# Schematic_Smart_watch_system.net
KiCad netlist of a schematic drawn in EasyEDA
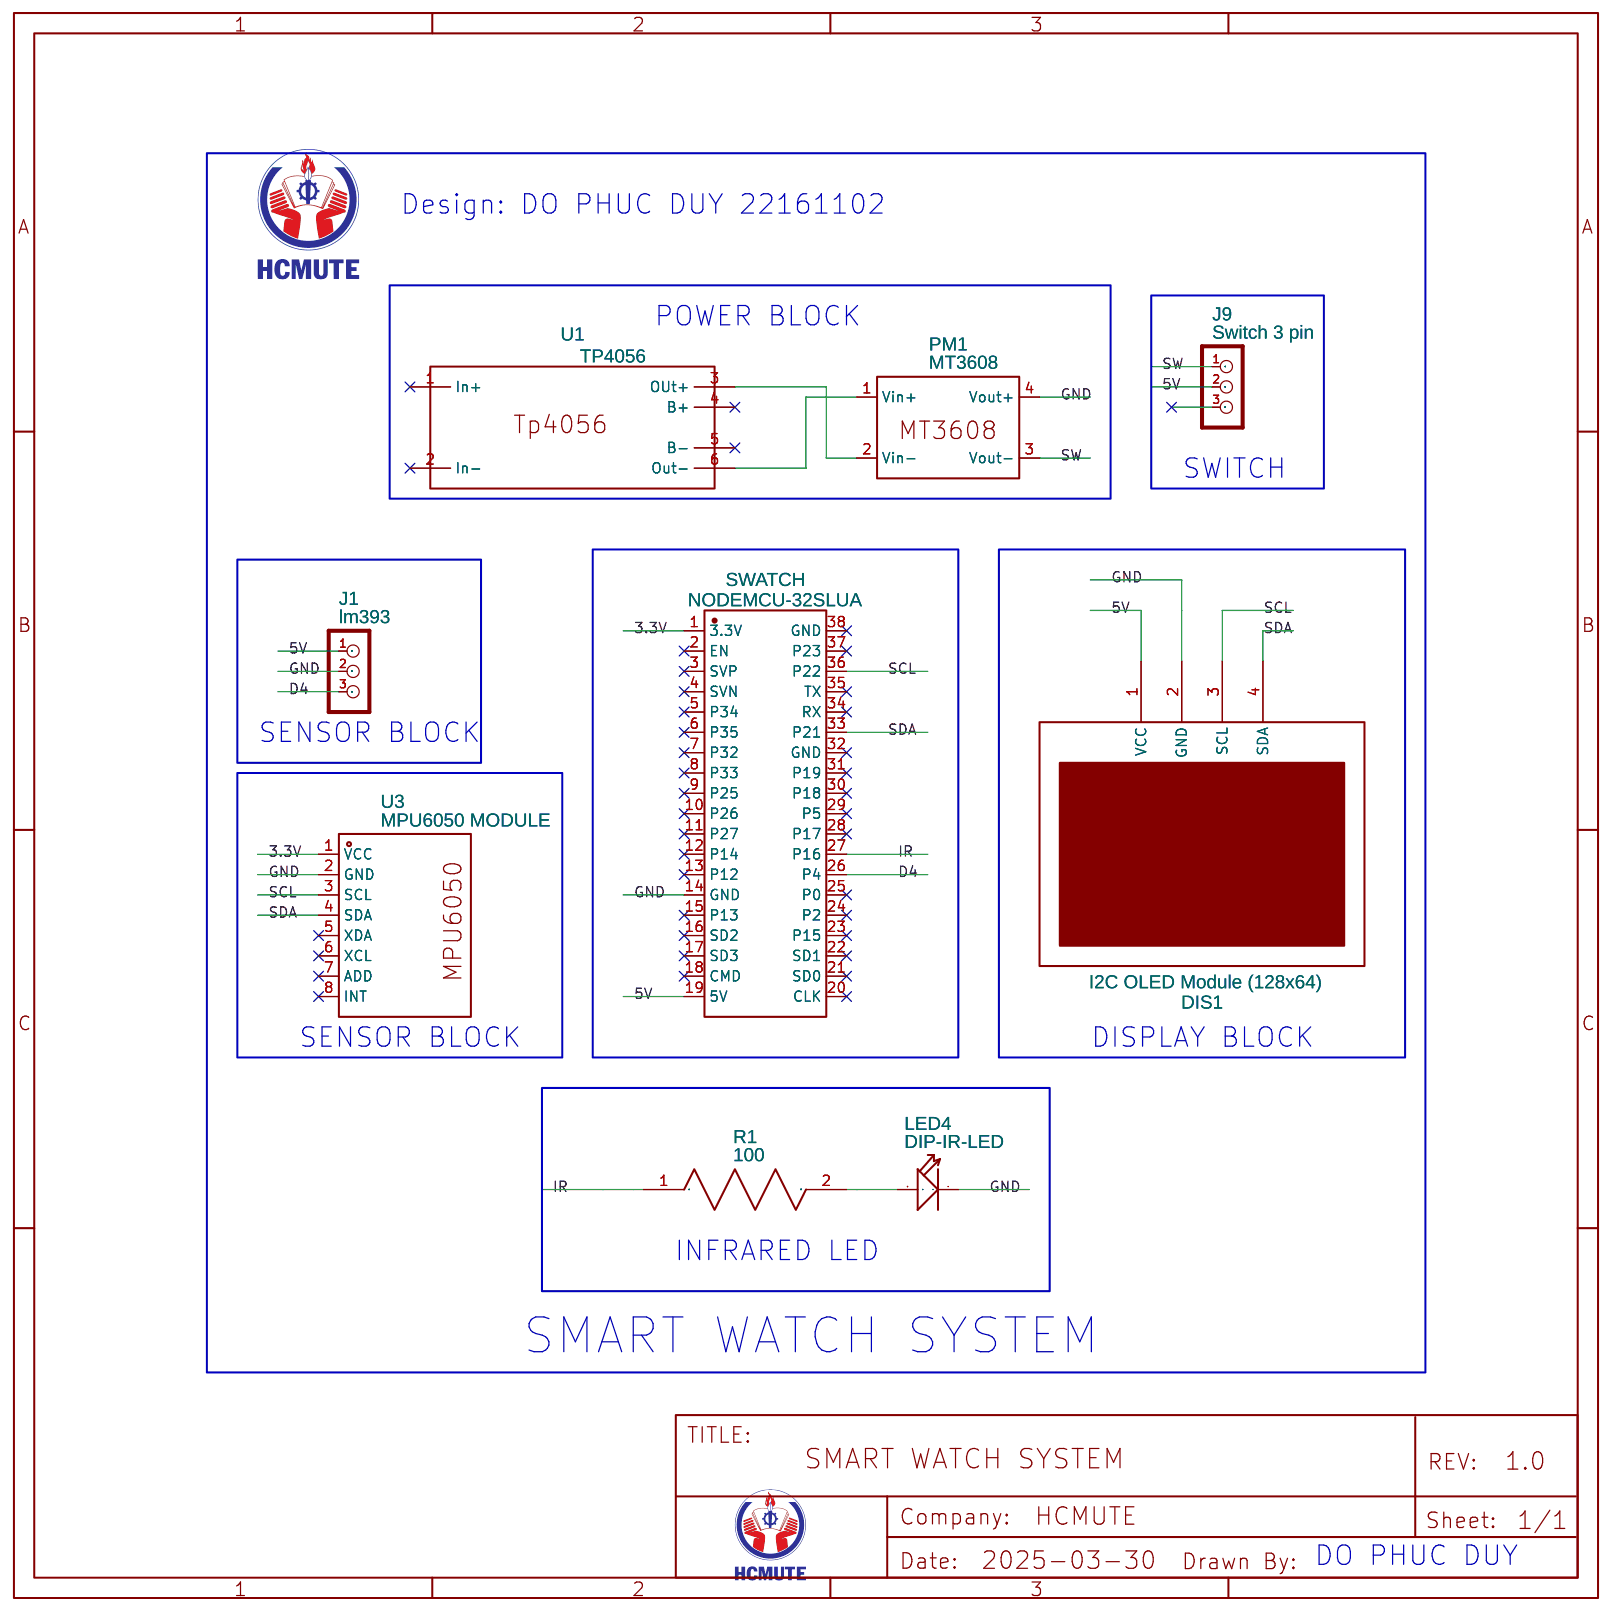
[diagram p0: schematic sheet]

(export (version "E")
  (design (tool "Eeschema 10.0.6"))
  (components
    (comp (ref "DIS1")
      (value "I2C OLED Module (128x64)")
      (fields (field (name "Manufacturer Part") "SSD1306"))
      (libsource (lib "") (part "I2C OLED Module (128x64)"))
    )
    (comp (ref "J1") (value "lm393") (libsource (lib "") (part "CON_HEADER_1X03")))
    (comp (ref "J9") (value "Switch 3 pin") (libsource (lib "") (part "CON_HEADER_1X03")))
    (comp (ref "LED4")
      (value "DIP-IR-LED")
      (fields (field (name "Manufacturer Part") "IR523B-W60W1"))
      (libsource (lib "") (part "DIP-IR-LED-940NM(2P-D5MM)"))
    )
    (comp (ref "PM1") (value "MT3608") (libsource (lib "") (part "MT3608 MODULE_new")))
    (comp (ref "R1") (value "100") (libsource (lib "") (part "1K ohm resistor")))
    (comp (ref "SWATCH")
      (value "NODEMCU-32SLUA")
      (fields
        (field (name "Manufacturer Part") "NodeMCU-32SLua")
        (field (name "Manufacturer") "Ai-Thinker(安信可)")
      )
      (libsource (lib "") (part "NODEMCU-32SLUA"))
    )
    (comp (ref "U1")
      (value "TP4056")
      (fields (field (name "Manufacturer Part") "TP4056 Lithium Battery Charger Module"))
      (libsource (lib "") (part "TP4056 Lithium Battery Charger Module"))
    )
    (comp (ref "U3")
      (value "MPU6050 MODULE")
      (fields (field (name "Manufacturer Part") "MPU6050"))
      (libsource (lib "") (part "MPU6050 MODULE"))
    )
  )
  (nets
    (net (code "1") (name "/3.3V") (class "Default")
      (node (ref "SWATCH") (pin "1") (pinfunction "3.3V_1") (pintype "unspecified"))
      (node (ref "U3") (pin "1") (pinfunction "VCC_1") (pintype "passive"))
    )
    (net (code "2") (name "/5V") (class "Default")
      (node (ref "DIS1") (pin "1") (pinfunction "VCC_1") (pintype "bidirectional"))
      (node (ref "J1") (pin "1") (pinfunction "1_1") (pintype "unspecified"))
      (node (ref "J9") (pin "2") (pinfunction "2_2") (pintype "unspecified"))
      (node (ref "SWATCH") (pin "19") (pinfunction "5V_19") (pintype "unspecified"))
    )
    (net (code "3") (name "/D4") (class "Default")
      (node (ref "J1") (pin "3") (pinfunction "3_3") (pintype "unspecified"))
      (node (ref "SWATCH") (pin "26") (pinfunction "P4_26") (pintype "unspecified"))
    )
    (net (code "4") (name "/GND") (class "Default")
      (node (ref "DIS1") (pin "2") (pinfunction "GND_2") (pintype "bidirectional"))
      (node (ref "J1") (pin "2") (pinfunction "2_2") (pintype "unspecified"))
      (node (ref "LED4") (pin "-") (pinfunction "-_-") (pintype "unspecified"))
      (node (ref "PM1") (pin "4") (pinfunction "Vout+_4") (pintype "unspecified"))
      (node (ref "SWATCH") (pin "14") (pinfunction "GND_14") (pintype "unspecified"))
      (node (ref "U3") (pin "2") (pinfunction "GND_2") (pintype "passive"))
    )
    (net (code "5") (name "/IR") (class "Default")
      (node (ref "R1") (pin "1") (pinfunction "1_1") (pintype "unspecified"))
      (node (ref "SWATCH") (pin "27") (pinfunction "P16_27") (pintype "unspecified"))
    )
    (net (code "6") (name "/SCL") (class "Default")
      (node (ref "DIS1") (pin "3") (pinfunction "SCL_3") (pintype "bidirectional"))
      (node (ref "SWATCH") (pin "36") (pinfunction "P22_36") (pintype "unspecified"))
      (node (ref "U3") (pin "3") (pinfunction "SCL_3") (pintype "input"))
    )
    (net (code "7") (name "/SDA") (class "Default")
      (node (ref "DIS1") (pin "4") (pinfunction "SDA_4") (pintype "bidirectional"))
      (node (ref "SWATCH") (pin "33") (pinfunction "P21_33") (pintype "unspecified"))
      (node (ref "U3") (pin "4") (pinfunction "SDA_4") (pintype "bidirectional"))
    )
    (net (code "8") (name "/SW") (class "Default")
      (node (ref "J9") (pin "1") (pinfunction "1_1") (pintype "unspecified"))
      (node (ref "PM1") (pin "3") (pinfunction "Vout-_3") (pintype "unspecified"))
    )
    (net (code "9") (name "Net-(LED4-Pad+)") (class "Default")
      (node (ref "LED4") (pin "+") (pinfunction "+_+") (pintype "unspecified"))
      (node (ref "R1") (pin "2") (pinfunction "2_2") (pintype "unspecified"))
    )
    (net (code "10") (name "Net-(PM1-Vin+)") (class "Default")
      (node (ref "PM1") (pin "1") (pinfunction "Vin+_1") (pintype "unspecified"))
      (node (ref "U1") (pin "6") (pinfunction "Out-_6") (pintype "unspecified"))
    )
    (net (code "11") (name "Net-(PM1-Vin-)") (class "Default")
      (node (ref "PM1") (pin "2") (pinfunction "Vin-_2") (pintype "unspecified"))
      (node (ref "U1") (pin "3") (pinfunction "OUt+_3") (pintype "unspecified"))
    )
    (net (code "12") (name "unconnected-(J9-Pad3)") (class "Default")
      (node (ref "J9") (pin "3") (pinfunction "3_3") (pintype "unspecified+no_connect"))
    )
    (net (code "13") (name "unconnected-(SWATCH-CLK-Pad20)") (class "Default")
      (node (ref "SWATCH") (pin "20") (pinfunction "CLK_20") (pintype "unspecified+no_connect"))
    )
    (net (code "14") (name "unconnected-(SWATCH-CMD-Pad18)") (class "Default")
      (node (ref "SWATCH") (pin "18") (pinfunction "CMD_18") (pintype "unspecified+no_connect"))
    )
    (net (code "15") (name "unconnected-(SWATCH-EN-Pad2)") (class "Default")
      (node (ref "SWATCH") (pin "2") (pinfunction "EN_2") (pintype "unspecified+no_connect"))
    )
    (net (code "16") (name "unconnected-(SWATCH-GND-Pad32)") (class "Default")
      (node (ref "SWATCH") (pin "32") (pinfunction "GND_32") (pintype "unspecified+no_connect"))
    )
    (net (code "17") (name "unconnected-(SWATCH-GND-Pad38)") (class "Default")
      (node (ref "SWATCH") (pin "38") (pinfunction "GND_38") (pintype "unspecified+no_connect"))
    )
    (net (code "18") (name "unconnected-(SWATCH-P0-Pad25)") (class "Default")
      (node (ref "SWATCH") (pin "25") (pinfunction "P0_25") (pintype "unspecified+no_connect"))
    )
    (net (code "19") (name "unconnected-(SWATCH-P2-Pad24)") (class "Default")
      (node (ref "SWATCH") (pin "24") (pinfunction "P2_24") (pintype "unspecified+no_connect"))
    )
    (net (code "20") (name "unconnected-(SWATCH-P5-Pad29)") (class "Default")
      (node (ref "SWATCH") (pin "29") (pinfunction "P5_29") (pintype "unspecified+no_connect"))
    )
    (net (code "21") (name "unconnected-(SWATCH-P12-Pad13)") (class "Default")
      (node (ref "SWATCH") (pin "13") (pinfunction "P12_13") (pintype "unspecified+no_connect"))
    )
    (net (code "22") (name "unconnected-(SWATCH-P13-Pad15)") (class "Default")
      (node (ref "SWATCH") (pin "15") (pinfunction "P13_15") (pintype "unspecified+no_connect"))
    )
    (net (code "23") (name "unconnected-(SWATCH-P14-Pad12)") (class "Default")
      (node (ref "SWATCH") (pin "12") (pinfunction "P14_12") (pintype "unspecified+no_connect"))
    )
    (net (code "24") (name "unconnected-(SWATCH-P15-Pad23)") (class "Default")
      (node (ref "SWATCH") (pin "23") (pinfunction "P15_23") (pintype "unspecified+no_connect"))
    )
    (net (code "25") (name "unconnected-(SWATCH-P17-Pad28)") (class "Default")
      (node (ref "SWATCH") (pin "28") (pinfunction "P17_28") (pintype "unspecified+no_connect"))
    )
    (net (code "26") (name "unconnected-(SWATCH-P18-Pad30)") (class "Default")
      (node (ref "SWATCH") (pin "30") (pinfunction "P18_30") (pintype "unspecified+no_connect"))
    )
    (net (code "27") (name "unconnected-(SWATCH-P19-Pad31)") (class "Default")
      (node (ref "SWATCH") (pin "31") (pinfunction "P19_31") (pintype "unspecified+no_connect"))
    )
    (net (code "28") (name "unconnected-(SWATCH-P23-Pad37)") (class "Default")
      (node (ref "SWATCH") (pin "37") (pinfunction "P23_37") (pintype "unspecified+no_connect"))
    )
    (net (code "29") (name "unconnected-(SWATCH-P25-Pad9)") (class "Default")
      (node (ref "SWATCH") (pin "9") (pinfunction "P25_9") (pintype "unspecified+no_connect"))
    )
    (net (code "30") (name "unconnected-(SWATCH-P26-Pad10)") (class "Default")
      (node (ref "SWATCH") (pin "10") (pinfunction "P26_10") (pintype "unspecified+no_connect"))
    )
    (net (code "31") (name "unconnected-(SWATCH-P27-Pad11)") (class "Default")
      (node (ref "SWATCH") (pin "11") (pinfunction "P27_11") (pintype "unspecified+no_connect"))
    )
    (net (code "32") (name "unconnected-(SWATCH-P32-Pad7)") (class "Default")
      (node (ref "SWATCH") (pin "7") (pinfunction "P32_7") (pintype "unspecified+no_connect"))
    )
    (net (code "33") (name "unconnected-(SWATCH-P33-Pad8)") (class "Default")
      (node (ref "SWATCH") (pin "8") (pinfunction "P33_8") (pintype "unspecified+no_connect"))
    )
    (net (code "34") (name "unconnected-(SWATCH-P34-Pad5)") (class "Default")
      (node (ref "SWATCH") (pin "5") (pinfunction "P34_5") (pintype "unspecified+no_connect"))
    )
    (net (code "35") (name "unconnected-(SWATCH-P35-Pad6)") (class "Default")
      (node (ref "SWATCH") (pin "6") (pinfunction "P35_6") (pintype "unspecified+no_connect"))
    )
    (net (code "36") (name "unconnected-(SWATCH-RX-Pad34)") (class "Default")
      (node (ref "SWATCH") (pin "34") (pinfunction "RX_34") (pintype "unspecified+no_connect"))
    )
    (net (code "37") (name "unconnected-(SWATCH-SD0-Pad21)") (class "Default")
      (node (ref "SWATCH") (pin "21") (pinfunction "SD0_21") (pintype "unspecified+no_connect"))
    )
    (net (code "38") (name "unconnected-(SWATCH-SD1-Pad22)") (class "Default")
      (node (ref "SWATCH") (pin "22") (pinfunction "SD1_22") (pintype "unspecified+no_connect"))
    )
    (net (code "39") (name "unconnected-(SWATCH-SD2-Pad16)") (class "Default")
      (node (ref "SWATCH") (pin "16") (pinfunction "SD2_16") (pintype "unspecified+no_connect"))
    )
    (net (code "40") (name "unconnected-(SWATCH-SD3-Pad17)") (class "Default")
      (node (ref "SWATCH") (pin "17") (pinfunction "SD3_17") (pintype "unspecified+no_connect"))
    )
    (net (code "41") (name "unconnected-(SWATCH-SVN-Pad4)") (class "Default")
      (node (ref "SWATCH") (pin "4") (pinfunction "SVN_4") (pintype "unspecified+no_connect"))
    )
    (net (code "42") (name "unconnected-(SWATCH-SVP-Pad3)") (class "Default")
      (node (ref "SWATCH") (pin "3") (pinfunction "SVP_3") (pintype "unspecified+no_connect"))
    )
    (net (code "43") (name "unconnected-(SWATCH-TX-Pad35)") (class "Default")
      (node (ref "SWATCH") (pin "35") (pinfunction "TX_35") (pintype "unspecified+no_connect"))
    )
    (net (code "44") (name "unconnected-(U1-B+-Pad4)") (class "Default")
      (node (ref "U1") (pin "4") (pinfunction "B+_4") (pintype "unspecified+no_connect"))
    )
    (net (code "45") (name "unconnected-(U1-B--Pad5)") (class "Default")
      (node (ref "U1") (pin "5") (pinfunction "B-_5") (pintype "unspecified+no_connect"))
    )
    (net (code "46") (name "unconnected-(U1-In+-Pad1)") (class "Default")
      (node (ref "U1") (pin "1") (pinfunction "In+_1") (pintype "unspecified+no_connect"))
    )
    (net (code "47") (name "unconnected-(U1-In--Pad2)") (class "Default")
      (node (ref "U1") (pin "2") (pinfunction "In-_2") (pintype "unspecified+no_connect"))
    )
    (net (code "48") (name "unconnected-(U3-ADD-Pad7)") (class "Default")
      (node (ref "U3") (pin "7") (pinfunction "ADD_7") (pintype "unspecified+no_connect"))
    )
    (net (code "49") (name "unconnected-(U3-INT-Pad8)") (class "Default")
      (node (ref "U3") (pin "8") (pinfunction "INT_8") (pintype "unspecified+no_connect"))
    )
    (net (code "50") (name "unconnected-(U3-XCL-Pad6)") (class "Default")
      (node (ref "U3") (pin "6") (pinfunction "XCL_6") (pintype "input+no_connect"))
    )
    (net (code "51") (name "unconnected-(U3-XDA-Pad5)") (class "Default")
      (node (ref "U3") (pin "5") (pinfunction "XDA_5") (pintype "bidirectional+no_connect"))
    )
  )
)
